# MIDItrigger.net
KiCad netlist of a schematic drawn in EAGLE
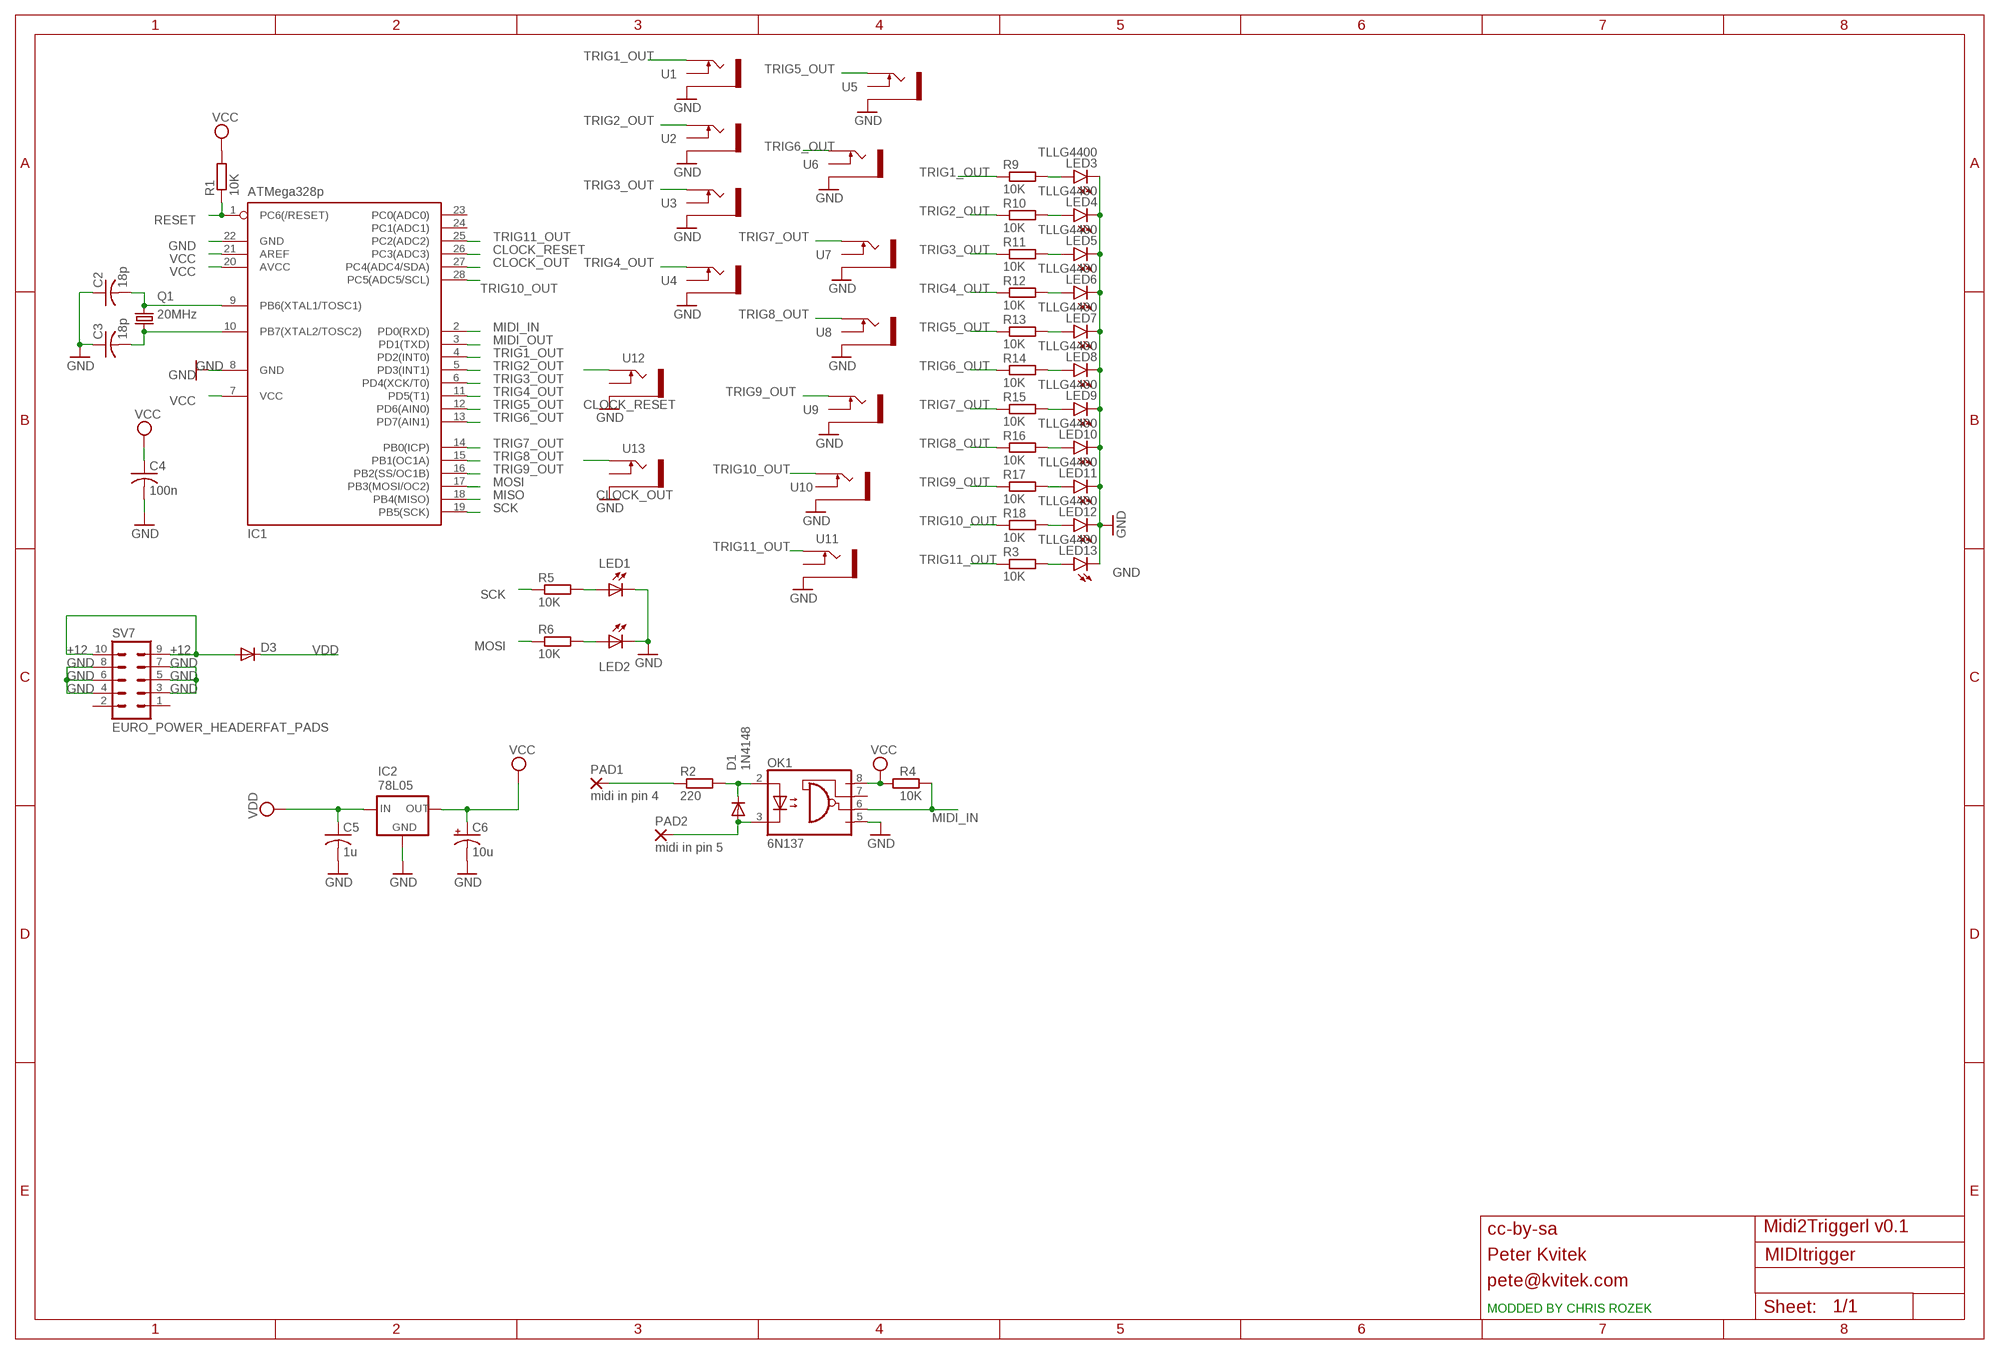
[diagram p0: schematic, sheet 1]

(export (version "E")
  (design (tool "Eeschema 10.0.6"))
  (components
    (comp (ref "C2")
      (value "18p")
      (footprint "eagle-import:C025-025X050")
      (libsource (lib "eagle-import") (part "C-US025-025X050"))
    )
    (comp (ref "C3")
      (value "18p")
      (footprint "eagle-import:C025-025X050")
      (libsource (lib "eagle-import") (part "C-US025-025X050"))
    )
    (comp (ref "C4")
      (value "100n")
      (footprint "eagle-import:C025-025X050")
      (libsource (lib "eagle-import") (part "C-US025-025X050"))
    )
    (comp (ref "C5")
      (value "1u")
      (footprint "eagle-import:C025-025X050")
      (libsource (lib "eagle-import") (part "C-US025-025X050"))
    )
    (comp (ref "C6")
      (value "10u")
      (footprint "eagle-import:E2,5-5")
      (libsource (lib "eagle-import") (part "CPOL-USE2.5-5"))
    )
    (comp (ref "D1")
      (value "1N4148")
      (footprint "eagle-import:DO35-7")
      (libsource (lib "eagle-import") (part "SMALL_DIODEDO35-7"))
    )
    (comp (ref "D3")
      (value "SMALL_DIODEDO35-7")
      (footprint "eagle-import:DO35-7")
      (libsource (lib "eagle-import") (part "SMALL_DIODEDO35-7"))
    )
    (comp (ref "IC1")
      (value "ATMega328p")
      (footprint "eagle-import:DIL28-3")
      (libsource (lib "eagle-import") (part "MEGA8-P"))
    )
    (comp (ref "IC2")
      (value "78L05")
      (footprint "eagle-import:78LXX")
      (libsource (lib "eagle-import") (part "78LXX"))
    )
    (comp (ref "LED1")
      (value "LED3MM")
      (footprint "eagle-import:LED3MM")
      (libsource (lib "eagle-import") (part "LED3MM"))
    )
    (comp (ref "LED2")
      (value "LED3MM")
      (footprint "eagle-import:LED3MM")
      (libsource (lib "eagle-import") (part "LED3MM"))
    )
    (comp (ref "LED3")
      (value "TLLG4400")
      (footprint "eagle-import:LED3MM")
      (fields (field (name "MF") "VISHAY SEMICONDUCTOR"))
      (libsource (lib "eagle-import") (part "TLLG4400"))
    )
    (comp (ref "LED4")
      (value "TLLG4400")
      (footprint "eagle-import:LED3MM")
      (fields (field (name "MF") "VISHAY SEMICONDUCTOR"))
      (libsource (lib "eagle-import") (part "TLLG4400"))
    )
    (comp (ref "LED5")
      (value "TLLG4400")
      (footprint "eagle-import:LED3MM")
      (fields (field (name "MF") "VISHAY SEMICONDUCTOR"))
      (libsource (lib "eagle-import") (part "TLLG4400"))
    )
    (comp (ref "LED6")
      (value "TLLG4400")
      (footprint "eagle-import:LED3MM")
      (fields (field (name "MF") "VISHAY SEMICONDUCTOR"))
      (libsource (lib "eagle-import") (part "TLLG4400"))
    )
    (comp (ref "LED7")
      (value "TLLG4400")
      (footprint "eagle-import:LED3MM")
      (fields (field (name "MF") "VISHAY SEMICONDUCTOR"))
      (libsource (lib "eagle-import") (part "TLLG4400"))
    )
    (comp (ref "LED8")
      (value "TLLG4400")
      (footprint "eagle-import:LED3MM")
      (fields (field (name "MF") "VISHAY SEMICONDUCTOR"))
      (libsource (lib "eagle-import") (part "TLLG4400"))
    )
    (comp (ref "LED9")
      (value "TLLG4400")
      (footprint "eagle-import:LED3MM")
      (fields (field (name "MF") "VISHAY SEMICONDUCTOR"))
      (libsource (lib "eagle-import") (part "TLLG4400"))
    )
    (comp (ref "LED10")
      (value "TLLG4400")
      (footprint "eagle-import:LED3MM")
      (fields (field (name "MF") "VISHAY SEMICONDUCTOR"))
      (libsource (lib "eagle-import") (part "TLLG4400"))
    )
    (comp (ref "LED11")
      (value "TLLG4400")
      (footprint "eagle-import:LED3MM")
      (fields (field (name "MF") "VISHAY SEMICONDUCTOR"))
      (libsource (lib "eagle-import") (part "TLLG4400"))
    )
    (comp (ref "LED12")
      (value "TLLG4400")
      (footprint "eagle-import:LED3MM")
      (fields (field (name "MF") "VISHAY SEMICONDUCTOR"))
      (libsource (lib "eagle-import") (part "TLLG4400"))
    )
    (comp (ref "LED13")
      (value "TLLG4400")
      (footprint "eagle-import:LED3MM")
      (fields (field (name "MF") "VISHAY SEMICONDUCTOR"))
      (libsource (lib "eagle-import") (part "TLLG4400"))
    )
    (comp (ref "OK1")
      (value "6N137")
      (footprint "eagle-import:DIL08")
      (libsource (lib "eagle-import") (part "6N137"))
    )
    (comp (ref "PAD1")
      (value "midi in pin 4")
      (footprint "eagle-import:2,54_1,1")
      (libsource (lib "eagle-import") (part "2,54/1,1"))
    )
    (comp (ref "PAD2")
      (value "midi in pin 5")
      (footprint "eagle-import:2,54_1,1")
      (libsource (lib "eagle-import") (part "2,54/1,1"))
    )
    (comp (ref "Q1")
      (value "20MHz")
      (footprint "eagle-import:HC49U-V")
      (libsource (lib "eagle-import") (part "CRYSTALHC49U-V"))
    )
    (comp (ref "R1")
      (value "10K")
      (footprint "eagle-import:VERTICAL_RESISTOR")
      (libsource (lib "eagle-import") (part "RESISTORVERTICAL"))
    )
    (comp (ref "R2")
      (value "220")
      (footprint "eagle-import:VERTICAL_RESISTOR")
      (libsource (lib "eagle-import") (part "RESISTORVERTICAL"))
    )
    (comp (ref "R3")
      (value "10K")
      (footprint "eagle-import:VERTICAL_RESISTOR")
      (libsource (lib "eagle-import") (part "RESISTORVERTICAL"))
    )
    (comp (ref "R4")
      (value "10K")
      (footprint "eagle-import:VERTICAL_RESISTOR")
      (libsource (lib "eagle-import") (part "RESISTORVERTICAL"))
    )
    (comp (ref "R5")
      (value "10K")
      (footprint "eagle-import:VERTICAL_RESISTOR")
      (libsource (lib "eagle-import") (part "RESISTORVERTICAL"))
    )
    (comp (ref "R6")
      (value "10K")
      (footprint "eagle-import:VERTICAL_RESISTOR")
      (libsource (lib "eagle-import") (part "RESISTORVERTICAL"))
    )
    (comp (ref "R9")
      (value "10K")
      (footprint "eagle-import:VERTICAL_RESISTOR")
      (libsource (lib "eagle-import") (part "RESISTORVERTICAL"))
    )
    (comp (ref "R10")
      (value "10K")
      (footprint "eagle-import:VERTICAL_RESISTOR")
      (libsource (lib "eagle-import") (part "RESISTORVERTICAL"))
    )
    (comp (ref "R11")
      (value "10K")
      (footprint "eagle-import:VERTICAL_RESISTOR")
      (libsource (lib "eagle-import") (part "RESISTORVERTICAL"))
    )
    (comp (ref "R12")
      (value "10K")
      (footprint "eagle-import:VERTICAL_RESISTOR")
      (libsource (lib "eagle-import") (part "RESISTORVERTICAL"))
    )
    (comp (ref "R13")
      (value "10K")
      (footprint "eagle-import:VERTICAL_RESISTOR")
      (libsource (lib "eagle-import") (part "RESISTORVERTICAL"))
    )
    (comp (ref "R14")
      (value "10K")
      (footprint "eagle-import:VERTICAL_RESISTOR")
      (libsource (lib "eagle-import") (part "RESISTORVERTICAL"))
    )
    (comp (ref "R15")
      (value "10K")
      (footprint "eagle-import:VERTICAL_RESISTOR")
      (libsource (lib "eagle-import") (part "RESISTORVERTICAL"))
    )
    (comp (ref "R16")
      (value "10K")
      (footprint "eagle-import:VERTICAL_RESISTOR")
      (libsource (lib "eagle-import") (part "RESISTORVERTICAL"))
    )
    (comp (ref "R17")
      (value "10K")
      (footprint "eagle-import:VERTICAL_RESISTOR")
      (libsource (lib "eagle-import") (part "RESISTORVERTICAL"))
    )
    (comp (ref "R18")
      (value "10K")
      (footprint "eagle-import:VERTICAL_RESISTOR")
      (libsource (lib "eagle-import") (part "RESISTORVERTICAL"))
    )
    (comp (ref "SV7")
      (value "EURO_POWER_HEADERFAT_PADS")
      (footprint "eagle-import:EURO_PWR_HEADER_FAT")
      (libsource (lib "eagle-import") (part "EURO_POWER_HEADERFAT_PADS"))
    )
    (comp (ref "U1")
      (value "THONKICONNNEW")
      (footprint "eagle-import:WQP-PJ301M-12_JACK")
      (libsource (lib "eagle-import") (part "THONKICONNNEW"))
    )
    (comp (ref "U2")
      (value "THONKICONNNEW")
      (footprint "eagle-import:WQP-PJ301M-12_JACK")
      (libsource (lib "eagle-import") (part "THONKICONNNEW"))
    )
    (comp (ref "U3")
      (value "THONKICONNNEW")
      (footprint "eagle-import:WQP-PJ301M-12_JACK")
      (libsource (lib "eagle-import") (part "THONKICONNNEW"))
    )
    (comp (ref "U4")
      (value "THONKICONNNEW")
      (footprint "eagle-import:WQP-PJ301M-12_JACK")
      (libsource (lib "eagle-import") (part "THONKICONNNEW"))
    )
    (comp (ref "U5")
      (value "THONKICONNNEW")
      (footprint "eagle-import:WQP-PJ301M-12_JACK")
      (libsource (lib "eagle-import") (part "THONKICONNNEW"))
    )
    (comp (ref "U6")
      (value "THONKICONNNEW")
      (footprint "eagle-import:WQP-PJ301M-12_JACK")
      (libsource (lib "eagle-import") (part "THONKICONNNEW"))
    )
    (comp (ref "U7")
      (value "THONKICONNNEW")
      (footprint "eagle-import:WQP-PJ301M-12_JACK")
      (libsource (lib "eagle-import") (part "THONKICONNNEW"))
    )
    (comp (ref "U8")
      (value "THONKICONNNEW")
      (footprint "eagle-import:WQP-PJ301M-12_JACK")
      (libsource (lib "eagle-import") (part "THONKICONNNEW"))
    )
    (comp (ref "U9")
      (value "THONKICONNNEW")
      (footprint "eagle-import:WQP-PJ301M-12_JACK")
      (libsource (lib "eagle-import") (part "THONKICONNNEW"))
    )
    (comp (ref "U10")
      (value "THONKICONNNEW")
      (footprint "eagle-import:WQP-PJ301M-12_JACK")
      (libsource (lib "eagle-import") (part "THONKICONNNEW"))
    )
    (comp (ref "U11")
      (value "THONKICONNNEW")
      (footprint "eagle-import:WQP-PJ301M-12_JACK")
      (libsource (lib "eagle-import") (part "THONKICONNNEW"))
    )
    (comp (ref "U12")
      (value "THONKICONNNEW")
      (footprint "eagle-import:WQP-PJ301M-12_JACK")
      (libsource (lib "eagle-import") (part "THONKICONNNEW"))
    )
    (comp (ref "U13")
      (value "THONKICONNNEW")
      (footprint "eagle-import:WQP-PJ301M-12_JACK")
      (libsource (lib "eagle-import") (part "THONKICONNNEW"))
    )
  )
  (nets
    (net (code "1") (name "/+12") (class "Default")
      (node (ref "D3") (pin "A") (pinfunction "A_A") (pintype "passive"))
      (node (ref "SV7") (pin "10") (pinfunction "10_10") (pintype "passive"))
      (node (ref "SV7") (pin "9") (pinfunction "9_9") (pintype "passive"))
    )
    (net (code "2") (name "/CLOCK_OUT") (class "Default")
      (node (ref "IC1") (pin "27") (pinfunction "PC4(ADC4/SDA)_27") (pintype "bidirectional"))
      (node (ref "U13") (pin "P$1_TIP") (pinfunction "TIP_P$1_TIP") (pintype "passive"))
    )
    (net (code "3") (name "/CLOCK_RESET") (class "Default")
      (node (ref "IC1") (pin "26") (pinfunction "PC3(ADC3)_26") (pintype "bidirectional"))
      (node (ref "U12") (pin "P$1_TIP") (pinfunction "TIP_P$1_TIP") (pintype "passive"))
    )
    (net (code "4") (name "/MIDI_IN") (class "Default")
      (node (ref "IC1") (pin "2") (pinfunction "PD0(RXD)_2") (pintype "bidirectional"))
      (node (ref "OK1") (pin "6") (pinfunction "VO_6") (pintype "passive"))
      (node (ref "R4") (pin "2") (pinfunction "2_2") (pintype "passive"))
    )
    (net (code "5") (name "/MIDI_OUT") (class "Default")
      (node (ref "IC1") (pin "3") (pinfunction "PD1(TXD)_3") (pintype "bidirectional"))
    )
    (net (code "6") (name "/MISO") (class "Default")
      (node (ref "IC1") (pin "18") (pinfunction "PB4(MISO)_18") (pintype "bidirectional"))
    )
    (net (code "7") (name "/MOSI") (class "Default")
      (node (ref "IC1") (pin "17") (pinfunction "PB3(MOSI/OC2)_17") (pintype "bidirectional"))
      (node (ref "R6") (pin "1") (pinfunction "1_1") (pintype "passive"))
    )
    (net (code "8") (name "/RESET") (class "Default")
      (node (ref "IC1") (pin "1") (pinfunction "PC6(/RESET)_1") (pintype "bidirectional"))
      (node (ref "R1") (pin "1") (pinfunction "1_1") (pintype "passive"))
    )
    (net (code "9") (name "/SCK") (class "Default")
      (node (ref "IC1") (pin "19") (pinfunction "PB5(SCK)_19") (pintype "bidirectional"))
      (node (ref "R5") (pin "1") (pinfunction "1_1") (pintype "passive"))
    )
    (net (code "10") (name "/TRIG1_OUT") (class "Default")
      (node (ref "IC1") (pin "4") (pinfunction "PD2(INT0)_4") (pintype "bidirectional"))
      (node (ref "R9") (pin "1") (pinfunction "1_1") (pintype "passive"))
      (node (ref "U1") (pin "P$1_TIP") (pinfunction "TIP_P$1_TIP") (pintype "passive"))
    )
    (net (code "11") (name "/TRIG2_OUT") (class "Default")
      (node (ref "IC1") (pin "5") (pinfunction "PD3(INT1)_5") (pintype "bidirectional"))
      (node (ref "R10") (pin "1") (pinfunction "1_1") (pintype "passive"))
      (node (ref "U2") (pin "P$1_TIP") (pinfunction "TIP_P$1_TIP") (pintype "passive"))
    )
    (net (code "12") (name "/TRIG3_OUT") (class "Default")
      (node (ref "IC1") (pin "6") (pinfunction "PD4(XCK/T0)_6") (pintype "bidirectional"))
      (node (ref "R11") (pin "1") (pinfunction "1_1") (pintype "passive"))
      (node (ref "U3") (pin "P$1_TIP") (pinfunction "TIP_P$1_TIP") (pintype "passive"))
    )
    (net (code "13") (name "/TRIG4_OUT") (class "Default")
      (node (ref "IC1") (pin "11") (pinfunction "PD5(T1)_11") (pintype "bidirectional"))
      (node (ref "R12") (pin "1") (pinfunction "1_1") (pintype "passive"))
      (node (ref "U4") (pin "P$1_TIP") (pinfunction "TIP_P$1_TIP") (pintype "passive"))
    )
    (net (code "14") (name "/TRIG5_OUT") (class "Default")
      (node (ref "IC1") (pin "12") (pinfunction "PD6(AIN0)_12") (pintype "bidirectional"))
      (node (ref "R13") (pin "1") (pinfunction "1_1") (pintype "passive"))
      (node (ref "U5") (pin "P$1_TIP") (pinfunction "TIP_P$1_TIP") (pintype "passive"))
    )
    (net (code "15") (name "/TRIG6_OUT") (class "Default")
      (node (ref "IC1") (pin "13") (pinfunction "PD7(AIN1)_13") (pintype "bidirectional"))
      (node (ref "R14") (pin "1") (pinfunction "1_1") (pintype "passive"))
      (node (ref "U6") (pin "P$1_TIP") (pinfunction "TIP_P$1_TIP") (pintype "passive"))
    )
    (net (code "16") (name "/TRIG7_OUT") (class "Default")
      (node (ref "IC1") (pin "14") (pinfunction "PB0(ICP)_14") (pintype "bidirectional"))
      (node (ref "R15") (pin "1") (pinfunction "1_1") (pintype "passive"))
      (node (ref "U7") (pin "P$1_TIP") (pinfunction "TIP_P$1_TIP") (pintype "passive"))
    )
    (net (code "17") (name "/TRIG8_OUT") (class "Default")
      (node (ref "IC1") (pin "15") (pinfunction "PB1(OC1A)_15") (pintype "bidirectional"))
      (node (ref "R16") (pin "1") (pinfunction "1_1") (pintype "passive"))
      (node (ref "U8") (pin "P$1_TIP") (pinfunction "TIP_P$1_TIP") (pintype "passive"))
    )
    (net (code "18") (name "/TRIG9_OUT") (class "Default")
      (node (ref "IC1") (pin "16") (pinfunction "PB2(SS/OC1B)_16") (pintype "bidirectional"))
      (node (ref "R17") (pin "1") (pinfunction "1_1") (pintype "passive"))
      (node (ref "U9") (pin "P$1_TIP") (pinfunction "TIP_P$1_TIP") (pintype "passive"))
    )
    (net (code "19") (name "/TRIG10_OUT") (class "Default")
      (node (ref "IC1") (pin "28") (pinfunction "PC5(ADC5/SCL)_28") (pintype "bidirectional"))
      (node (ref "R18") (pin "1") (pinfunction "1_1") (pintype "passive"))
      (node (ref "U10") (pin "P$1_TIP") (pinfunction "TIP_P$1_TIP") (pintype "passive"))
    )
    (net (code "20") (name "/TRIG11_OUT") (class "Default")
      (node (ref "IC1") (pin "25") (pinfunction "PC2(ADC2)_25") (pintype "bidirectional"))
      (node (ref "R3") (pin "1") (pinfunction "1_1") (pintype "passive"))
      (node (ref "U11") (pin "P$1_TIP") (pinfunction "TIP_P$1_TIP") (pintype "passive"))
    )
    (net (code "21") (name "GND") (class "Default")
      (node (ref "C2") (pin "1") (pinfunction "1_1") (pintype "passive"))
      (node (ref "C3") (pin "1") (pinfunction "1_1") (pintype "passive"))
      (node (ref "C4") (pin "2") (pinfunction "2_2") (pintype "passive"))
      (node (ref "C5") (pin "2") (pinfunction "2_2") (pintype "passive"))
      (node (ref "C6") (pin "-") (pinfunction "-_-") (pintype "passive"))
      (node (ref "IC1") (pin "22") (pinfunction "GND_22") (pintype "power_in"))
      (node (ref "IC1") (pin "8") (pinfunction "GND_8") (pintype "power_in"))
      (node (ref "IC2") (pin "GND") (pinfunction "GND_GND") (pintype "input"))
      (node (ref "LED1") (pin "K") (pinfunction "C_K") (pintype "passive"))
      (node (ref "LED10") (pin "K") (pinfunction "C_K") (pintype "passive"))
      (node (ref "LED11") (pin "K") (pinfunction "C_K") (pintype "passive"))
      (node (ref "LED12") (pin "K") (pinfunction "C_K") (pintype "passive"))
      (node (ref "LED13") (pin "K") (pinfunction "C_K") (pintype "passive"))
      (node (ref "LED2") (pin "K") (pinfunction "C_K") (pintype "passive"))
      (node (ref "LED3") (pin "K") (pinfunction "C_K") (pintype "passive"))
      (node (ref "LED4") (pin "K") (pinfunction "C_K") (pintype "passive"))
      (node (ref "LED5") (pin "K") (pinfunction "C_K") (pintype "passive"))
      (node (ref "LED6") (pin "K") (pinfunction "C_K") (pintype "passive"))
      (node (ref "LED7") (pin "K") (pinfunction "C_K") (pintype "passive"))
      (node (ref "LED8") (pin "K") (pinfunction "C_K") (pintype "passive"))
      (node (ref "LED9") (pin "K") (pinfunction "C_K") (pintype "passive"))
      (node (ref "OK1") (pin "5") (pinfunction "GND_5") (pintype "passive"))
      (node (ref "SV7") (pin "3") (pinfunction "3_3") (pintype "passive"))
      (node (ref "SV7") (pin "4") (pinfunction "4_4") (pintype "passive"))
      (node (ref "SV7") (pin "5") (pinfunction "5_5") (pintype "passive"))
      (node (ref "SV7") (pin "6") (pinfunction "6_6") (pintype "passive"))
      (node (ref "SV7") (pin "7") (pinfunction "7_7") (pintype "passive"))
      (node (ref "SV7") (pin "8") (pinfunction "8_8") (pintype "passive"))
      (node (ref "U1") (pin "P$3_SLEEVE") (pinfunction "SLEEVE_P$3_SLEEVE") (pintype "passive"))
      (node (ref "U10") (pin "P$3_SLEEVE") (pinfunction "SLEEVE_P$3_SLEEVE") (pintype "passive"))
      (node (ref "U11") (pin "P$3_SLEEVE") (pinfunction "SLEEVE_P$3_SLEEVE") (pintype "passive"))
      (node (ref "U12") (pin "P$3_SLEEVE") (pinfunction "SLEEVE_P$3_SLEEVE") (pintype "passive"))
      (node (ref "U13") (pin "P$3_SLEEVE") (pinfunction "SLEEVE_P$3_SLEEVE") (pintype "passive"))
      (node (ref "U2") (pin "P$3_SLEEVE") (pinfunction "SLEEVE_P$3_SLEEVE") (pintype "passive"))
      (node (ref "U3") (pin "P$3_SLEEVE") (pinfunction "SLEEVE_P$3_SLEEVE") (pintype "passive"))
      (node (ref "U4") (pin "P$3_SLEEVE") (pinfunction "SLEEVE_P$3_SLEEVE") (pintype "passive"))
      (node (ref "U5") (pin "P$3_SLEEVE") (pinfunction "SLEEVE_P$3_SLEEVE") (pintype "passive"))
      (node (ref "U6") (pin "P$3_SLEEVE") (pinfunction "SLEEVE_P$3_SLEEVE") (pintype "passive"))
      (node (ref "U7") (pin "P$3_SLEEVE") (pinfunction "SLEEVE_P$3_SLEEVE") (pintype "passive"))
      (node (ref "U8") (pin "P$3_SLEEVE") (pinfunction "SLEEVE_P$3_SLEEVE") (pintype "passive"))
      (node (ref "U9") (pin "P$3_SLEEVE") (pinfunction "SLEEVE_P$3_SLEEVE") (pintype "passive"))
    )
    (net (code "22") (name "Net-(IC1-PB6(XTAL1{slash}TOSC1))") (class "Default")
      (node (ref "C2") (pin "2") (pinfunction "2_2") (pintype "passive"))
      (node (ref "IC1") (pin "9") (pinfunction "PB6(XTAL1/TOSC1)_9") (pintype "bidirectional"))
      (node (ref "Q1") (pin "2") (pinfunction "2_2") (pintype "passive"))
    )
    (net (code "23") (name "Net-(IC1-PB7(XTAL2{slash}TOSC2))") (class "Default")
      (node (ref "C3") (pin "2") (pinfunction "2_2") (pintype "passive"))
      (node (ref "IC1") (pin "10") (pinfunction "PB7(XTAL2/TOSC2)_10") (pintype "bidirectional"))
      (node (ref "Q1") (pin "1") (pinfunction "1_1") (pintype "passive"))
    )
    (net (code "24") (name "Net-(LED1-PadA)") (class "Default")
      (node (ref "LED1") (pin "A") (pinfunction "A_A") (pintype "passive"))
      (node (ref "R5") (pin "2") (pinfunction "2_2") (pintype "passive"))
    )
    (net (code "25") (name "Net-(LED2-PadA)") (class "Default")
      (node (ref "LED2") (pin "A") (pinfunction "A_A") (pintype "passive"))
      (node (ref "R6") (pin "2") (pinfunction "2_2") (pintype "passive"))
    )
    (net (code "26") (name "Net-(LED3-PadA)") (class "Default")
      (node (ref "LED3") (pin "A") (pinfunction "A_A") (pintype "passive"))
      (node (ref "R9") (pin "2") (pinfunction "2_2") (pintype "passive"))
    )
    (net (code "27") (name "Net-(LED4-PadA)") (class "Default")
      (node (ref "LED4") (pin "A") (pinfunction "A_A") (pintype "passive"))
      (node (ref "R10") (pin "2") (pinfunction "2_2") (pintype "passive"))
    )
    (net (code "28") (name "Net-(LED5-PadA)") (class "Default")
      (node (ref "LED5") (pin "A") (pinfunction "A_A") (pintype "passive"))
      (node (ref "R11") (pin "2") (pinfunction "2_2") (pintype "passive"))
    )
    (net (code "29") (name "Net-(LED6-PadA)") (class "Default")
      (node (ref "LED6") (pin "A") (pinfunction "A_A") (pintype "passive"))
      (node (ref "R12") (pin "2") (pinfunction "2_2") (pintype "passive"))
    )
    (net (code "30") (name "Net-(LED7-PadA)") (class "Default")
      (node (ref "LED7") (pin "A") (pinfunction "A_A") (pintype "passive"))
      (node (ref "R13") (pin "2") (pinfunction "2_2") (pintype "passive"))
    )
    (net (code "31") (name "Net-(LED8-PadA)") (class "Default")
      (node (ref "LED8") (pin "A") (pinfunction "A_A") (pintype "passive"))
      (node (ref "R14") (pin "2") (pinfunction "2_2") (pintype "passive"))
    )
    (net (code "32") (name "Net-(LED9-PadA)") (class "Default")
      (node (ref "LED9") (pin "A") (pinfunction "A_A") (pintype "passive"))
      (node (ref "R15") (pin "2") (pinfunction "2_2") (pintype "passive"))
    )
    (net (code "33") (name "Net-(LED10-PadA)") (class "Default")
      (node (ref "LED10") (pin "A") (pinfunction "A_A") (pintype "passive"))
      (node (ref "R16") (pin "2") (pinfunction "2_2") (pintype "passive"))
    )
    (net (code "34") (name "Net-(LED11-PadA)") (class "Default")
      (node (ref "LED11") (pin "A") (pinfunction "A_A") (pintype "passive"))
      (node (ref "R17") (pin "2") (pinfunction "2_2") (pintype "passive"))
    )
    (net (code "35") (name "Net-(LED12-PadA)") (class "Default")
      (node (ref "LED12") (pin "A") (pinfunction "A_A") (pintype "passive"))
      (node (ref "R18") (pin "2") (pinfunction "2_2") (pintype "passive"))
    )
    (net (code "36") (name "Net-(LED13-PadA)") (class "Default")
      (node (ref "LED13") (pin "A") (pinfunction "A_A") (pintype "passive"))
      (node (ref "R3") (pin "2") (pinfunction "2_2") (pintype "passive"))
    )
    (net (code "37") (name "Net-(OK1-A)") (class "Default")
      (node (ref "D1") (pin "C") (pinfunction "C_C") (pintype "passive"))
      (node (ref "OK1") (pin "2") (pinfunction "A_2") (pintype "passive"))
      (node (ref "R2") (pin "2") (pinfunction "2_2") (pintype "passive"))
    )
    (net (code "38") (name "Net-(OK1-C)") (class "Default")
      (node (ref "D1") (pin "A") (pinfunction "A_A") (pintype "passive"))
      (node (ref "OK1") (pin "3") (pinfunction "C_3") (pintype "passive"))
      (node (ref "PAD2") (pin "1") (pinfunction "P_1") (pintype "passive"))
    )
    (net (code "39") (name "Net-(PAD1-P)") (class "Default")
      (node (ref "PAD1") (pin "1") (pinfunction "P_1") (pintype "passive"))
      (node (ref "R2") (pin "1") (pinfunction "1_1") (pintype "passive"))
    )
    (net (code "40") (name "VCC") (class "Default")
      (node (ref "C4") (pin "1") (pinfunction "1_1") (pintype "passive"))
      (node (ref "C6") (pin "+") (pinfunction "+_+") (pintype "passive"))
      (node (ref "IC1") (pin "20") (pinfunction "AVCC_20") (pintype "power_in"))
      (node (ref "IC1") (pin "21") (pinfunction "AREF_21") (pintype "passive"))
      (node (ref "IC1") (pin "7") (pinfunction "VCC_7") (pintype "power_in"))
      (node (ref "IC2") (pin "OUT") (pinfunction "OUT_OUT") (pintype "passive"))
      (node (ref "OK1") (pin "8") (pinfunction "VCC_8") (pintype "passive"))
      (node (ref "R1") (pin "2") (pinfunction "2_2") (pintype "passive"))
      (node (ref "R4") (pin "1") (pinfunction "1_1") (pintype "passive"))
    )
    (net (code "41") (name "VDD") (class "Default")
      (node (ref "C5") (pin "1") (pinfunction "1_1") (pintype "passive"))
      (node (ref "D3") (pin "C") (pinfunction "C_C") (pintype "passive"))
      (node (ref "IC2") (pin "IN") (pinfunction "IN_IN") (pintype "input"))
    )
    (net (code "42") (name "unconnected-(IC1-PC0(ADC0)-Pad23)") (class "Default")
      (node (ref "IC1") (pin "23") (pinfunction "PC0(ADC0)_23") (pintype "bidirectional"))
    )
    (net (code "43") (name "unconnected-(IC1-PC1(ADC1)-Pad24)") (class "Default")
      (node (ref "IC1") (pin "24") (pinfunction "PC1(ADC1)_24") (pintype "bidirectional"))
    )
    (net (code "44") (name "unconnected-(OK1-VE-Pad7)") (class "Default")
      (node (ref "OK1") (pin "7") (pinfunction "VE_7") (pintype "passive"))
    )
    (net (code "45") (name "unconnected-(SV7-Pad1)") (class "Default")
      (node (ref "SV7") (pin "1") (pinfunction "1_1") (pintype "passive"))
    )
    (net (code "46") (name "unconnected-(SV7-Pad2)") (class "Default")
      (node (ref "SV7") (pin "2") (pinfunction "2_2") (pintype "passive"))
    )
    (net (code "47") (name "unconnected-(U1-SWITCH-PadP$2_SWITCH)") (class "Default")
      (node (ref "U1") (pin "P$2_SWITCH") (pinfunction "SWITCH_P$2_SWITCH") (pintype "passive"))
    )
    (net (code "48") (name "unconnected-(U2-SWITCH-PadP$2_SWITCH)") (class "Default")
      (node (ref "U2") (pin "P$2_SWITCH") (pinfunction "SWITCH_P$2_SWITCH") (pintype "passive"))
    )
    (net (code "49") (name "unconnected-(U3-SWITCH-PadP$2_SWITCH)") (class "Default")
      (node (ref "U3") (pin "P$2_SWITCH") (pinfunction "SWITCH_P$2_SWITCH") (pintype "passive"))
    )
    (net (code "50") (name "unconnected-(U4-SWITCH-PadP$2_SWITCH)") (class "Default")
      (node (ref "U4") (pin "P$2_SWITCH") (pinfunction "SWITCH_P$2_SWITCH") (pintype "passive"))
    )
    (net (code "51") (name "unconnected-(U5-SWITCH-PadP$2_SWITCH)") (class "Default")
      (node (ref "U5") (pin "P$2_SWITCH") (pinfunction "SWITCH_P$2_SWITCH") (pintype "passive"))
    )
    (net (code "52") (name "unconnected-(U6-SWITCH-PadP$2_SWITCH)") (class "Default")
      (node (ref "U6") (pin "P$2_SWITCH") (pinfunction "SWITCH_P$2_SWITCH") (pintype "passive"))
    )
    (net (code "53") (name "unconnected-(U7-SWITCH-PadP$2_SWITCH)") (class "Default")
      (node (ref "U7") (pin "P$2_SWITCH") (pinfunction "SWITCH_P$2_SWITCH") (pintype "passive"))
    )
    (net (code "54") (name "unconnected-(U8-SWITCH-PadP$2_SWITCH)") (class "Default")
      (node (ref "U8") (pin "P$2_SWITCH") (pinfunction "SWITCH_P$2_SWITCH") (pintype "passive"))
    )
    (net (code "55") (name "unconnected-(U9-SWITCH-PadP$2_SWITCH)") (class "Default")
      (node (ref "U9") (pin "P$2_SWITCH") (pinfunction "SWITCH_P$2_SWITCH") (pintype "passive"))
    )
    (net (code "56") (name "unconnected-(U10-SWITCH-PadP$2_SWITCH)") (class "Default")
      (node (ref "U10") (pin "P$2_SWITCH") (pinfunction "SWITCH_P$2_SWITCH") (pintype "passive"))
    )
    (net (code "57") (name "unconnected-(U11-SWITCH-PadP$2_SWITCH)") (class "Default")
      (node (ref "U11") (pin "P$2_SWITCH") (pinfunction "SWITCH_P$2_SWITCH") (pintype "passive"))
    )
    (net (code "58") (name "unconnected-(U12-SWITCH-PadP$2_SWITCH)") (class "Default")
      (node (ref "U12") (pin "P$2_SWITCH") (pinfunction "SWITCH_P$2_SWITCH") (pintype "passive"))
    )
    (net (code "59") (name "unconnected-(U13-SWITCH-PadP$2_SWITCH)") (class "Default")
      (node (ref "U13") (pin "P$2_SWITCH") (pinfunction "SWITCH_P$2_SWITCH") (pintype "passive"))
    )
  )
)
